# V831_CORE.net
KiCad netlist of a schematic drawn in Altium Designer
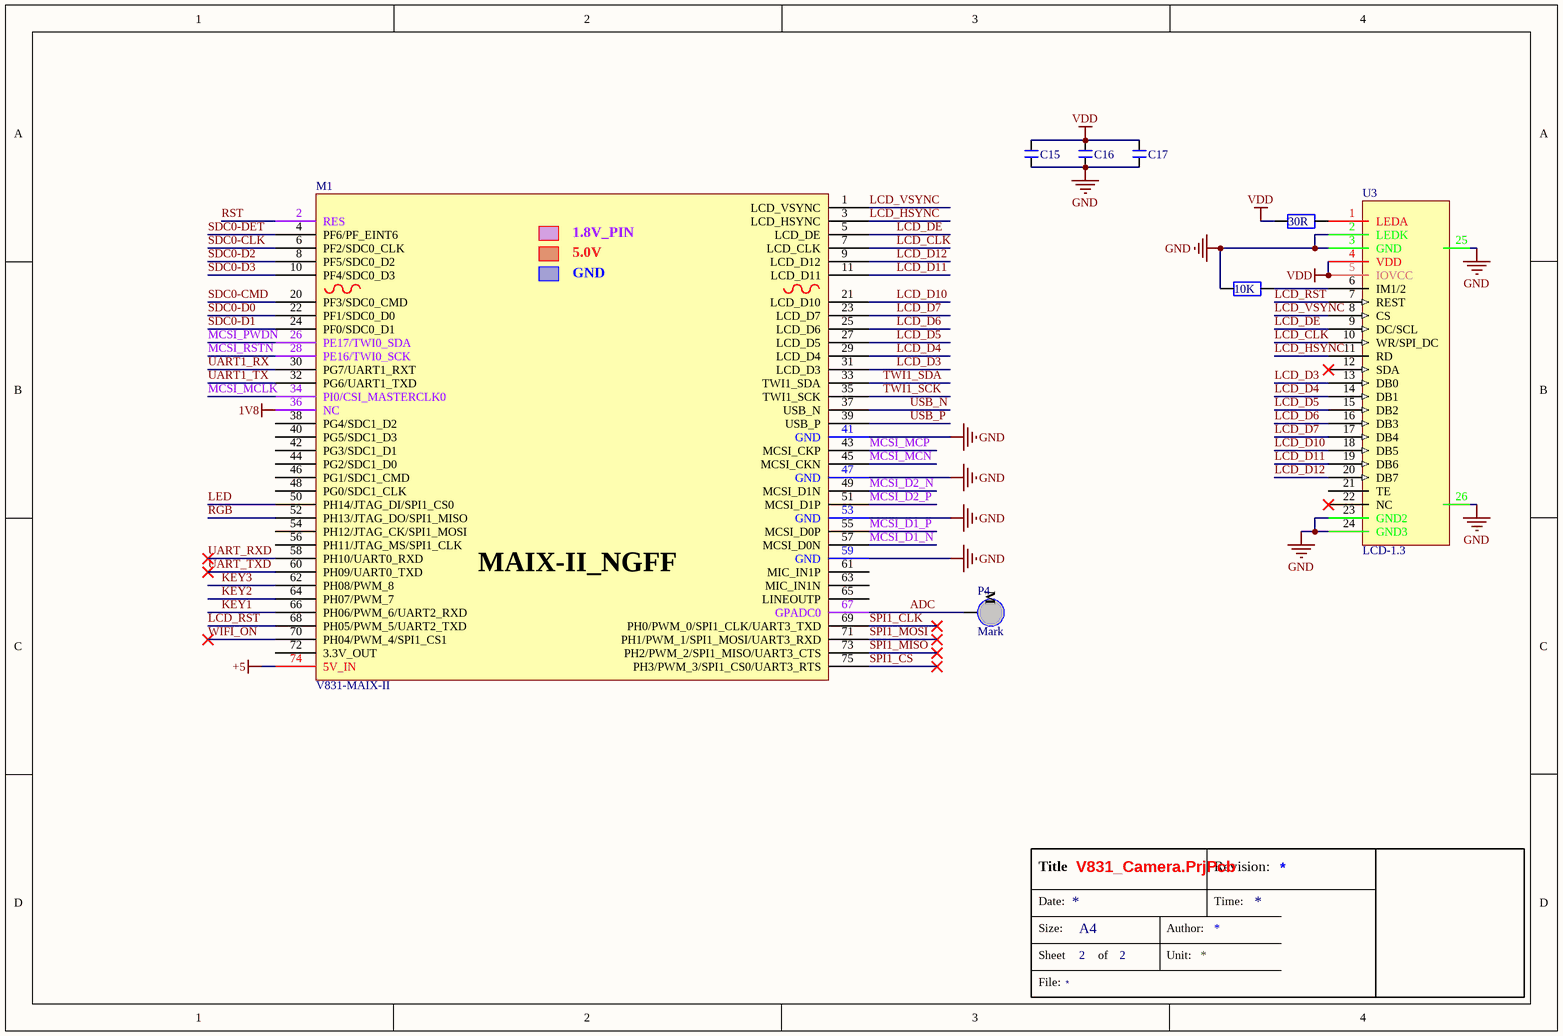
[diagram p0: V831_CORE.SchDoc]

(export (version "E")
  (design (tool "Eeschema 10.0.6"))
  (components
    (comp (ref "C15")
      (value "100NF")
      (footprint "CAP_0603")
      (description "CAP  12~50V")
      (libsource (lib "User") (part "CAP"))
    )
    (comp (ref "C16")
      (value "100NF")
      (footprint "CAP_0603")
      (description "CAP  12~50V")
      (libsource (lib "User") (part "CAP"))
    )
    (comp (ref "C17")
      (value "100NF")
      (footprint "CAP_0603")
      (description "CAP  12~50V")
      (libsource (lib "User") (part "CAP"))
    )
    (comp (ref "M1")
      (value "V831-MAIX-II")
      (footprint "V831_NAIX-II")
      (description "Sipeed-v831-M2dock")
      (libsource (lib "User") (part "V831_MAIX-II"))
    )
    (comp (ref "P4") (value "Mark") (footprint "Mark") (libsource (lib "User") (part "Mark")))
    (comp (ref "R15")
      (value "30R")
      (footprint "RESC_0603_2")
      (description "RES 贴片")
      (libsource (lib "User") (part "RES"))
    )
    (comp (ref "R16")
      (value "10K")
      (footprint "RESC_0603_2")
      (description "RES 贴片")
      (libsource (lib "User") (part "RES"))
    )
    (comp (ref "U3")
      (value "LCD-1.3")
      (footprint "FPC-24PIN-FB-Mirror")
      (description "SHOW  24Pin")
      (libsource (lib "User") (part "LCD_1.3"))
    )
  )
  (nets
    (net (code "1") (name "+5") (class "Default")
      (node (ref "M1") (pin "74") (pinfunction "5V_IN_74") (pintype "passive"))
    )
    (net (code "2") (name "/ADC") (class "Default")
      (node (ref "M1") (pin "67") (pinfunction "GPADC0_67") (pintype "passive"))
      (node (ref "P4") (pin "1") (pinfunction "1_1") (pintype "passive"))
    )
    (net (code "3") (name "/KEY1") (class "Default")
      (node (ref "M1") (pin "66") (pinfunction "PH06/PWM_6/UART2_RXD_66") (pintype "passive"))
    )
    (net (code "4") (name "/KEY2") (class "Default")
      (node (ref "M1") (pin "64") (pinfunction "PH07/PWM_7_64") (pintype "passive"))
    )
    (net (code "5") (name "/KEY3") (class "Default")
      (node (ref "M1") (pin "62") (pinfunction "PH08/PWM_8_62") (pintype "passive"))
    )
    (net (code "6") (name "/LCD_CLK") (class "Default")
      (node (ref "M1") (pin "7") (pinfunction "LCD_CLK_7") (pintype "passive"))
      (node (ref "U3") (pin "10") (pinfunction "WR/SPI_DC_10") (pintype "input"))
    )
    (net (code "7") (name "/LCD_D3") (class "Default")
      (node (ref "M1") (pin "31") (pinfunction "LCD_D3_31") (pintype "passive"))
      (node (ref "U3") (pin "13") (pinfunction "DB0_13") (pintype "input"))
    )
    (net (code "8") (name "/LCD_D4") (class "Default")
      (node (ref "M1") (pin "29") (pinfunction "LCD_D4_29") (pintype "passive"))
      (node (ref "U3") (pin "14") (pinfunction "DB1_14") (pintype "input"))
    )
    (net (code "9") (name "/LCD_D5") (class "Default")
      (node (ref "M1") (pin "27") (pinfunction "LCD_D5_27") (pintype "passive"))
      (node (ref "U3") (pin "15") (pinfunction "DB2_15") (pintype "input"))
    )
    (net (code "10") (name "/LCD_D6") (class "Default")
      (node (ref "M1") (pin "25") (pinfunction "LCD_D6_25") (pintype "passive"))
      (node (ref "U3") (pin "16") (pinfunction "DB3_16") (pintype "input"))
    )
    (net (code "11") (name "/LCD_D7") (class "Default")
      (node (ref "M1") (pin "23") (pinfunction "LCD_D7_23") (pintype "passive"))
      (node (ref "U3") (pin "17") (pinfunction "DB4_17") (pintype "input"))
    )
    (net (code "12") (name "/LCD_D10") (class "Default")
      (node (ref "M1") (pin "21") (pinfunction "LCD_D10_21") (pintype "passive"))
      (node (ref "U3") (pin "18") (pinfunction "DB5_18") (pintype "input"))
    )
    (net (code "13") (name "/LCD_D11") (class "Default")
      (node (ref "M1") (pin "11") (pinfunction "LCD_D11_11") (pintype "passive"))
      (node (ref "U3") (pin "19") (pinfunction "DB6_19") (pintype "input"))
    )
    (net (code "14") (name "/LCD_D12") (class "Default")
      (node (ref "M1") (pin "9") (pinfunction "LCD_D12_9") (pintype "passive"))
      (node (ref "U3") (pin "20") (pinfunction "DB7_20") (pintype "input"))
    )
    (net (code "15") (name "/LCD_DE") (class "Default")
      (node (ref "M1") (pin "5") (pinfunction "LCD_DE_5") (pintype "passive"))
      (node (ref "U3") (pin "9") (pinfunction "DC/SCL_9") (pintype "input"))
    )
    (net (code "16") (name "/LCD_HSYNC") (class "Default")
      (node (ref "M1") (pin "3") (pinfunction "LCD_HSYNC_3") (pintype "passive"))
      (node (ref "U3") (pin "11") (pinfunction "RD_11") (pintype "passive"))
    )
    (net (code "17") (name "/LCD_RST") (class "Default")
      (node (ref "M1") (pin "68") (pinfunction "PH05/PWM_5/UART2_TXD_68") (pintype "passive"))
      (node (ref "U3") (pin "7") (pinfunction "REST_7") (pintype "input"))
    )
    (net (code "18") (name "/LCD_VSYNC") (class "Default")
      (node (ref "M1") (pin "1") (pinfunction "LCD_VSYNC_1") (pintype "passive"))
      (node (ref "U3") (pin "8") (pinfunction "CS_8") (pintype "input"))
    )
    (net (code "19") (name "/LED") (class "Default")
      (node (ref "M1") (pin "50") (pinfunction "PH14/JTAG_DI/SPI1_CS0_50") (pintype "passive"))
    )
    (net (code "20") (name "/MCSI_D1_N") (class "Default")
      (node (ref "M1") (pin "57") (pinfunction "MCSI_D0N_57") (pintype "passive"))
    )
    (net (code "21") (name "/MCSI_D1_P") (class "Default")
      (node (ref "M1") (pin "55") (pinfunction "MCSI_D0P_55") (pintype "passive"))
    )
    (net (code "22") (name "/MCSI_D2_N") (class "Default")
      (node (ref "M1") (pin "49") (pinfunction "MCSI_D1N_49") (pintype "passive"))
    )
    (net (code "23") (name "/MCSI_D2_P") (class "Default")
      (node (ref "M1") (pin "51") (pinfunction "MCSI_D1P_51") (pintype "passive"))
    )
    (net (code "24") (name "/MCSI_MCLK") (class "Default")
      (node (ref "M1") (pin "34") (pinfunction "PI0/CSI_MASTERCLK0_34") (pintype "passive"))
    )
    (net (code "25") (name "/MCSI_MCN") (class "Default")
      (node (ref "M1") (pin "45") (pinfunction "MCSI_CKN_45") (pintype "passive"))
    )
    (net (code "26") (name "/MCSI_MCP") (class "Default")
      (node (ref "M1") (pin "43") (pinfunction "MCSI_CKP_43") (pintype "passive"))
    )
    (net (code "27") (name "/MCSI_PWDN") (class "Default")
      (node (ref "M1") (pin "26") (pinfunction "PE17/TWI0_SDA_26") (pintype "passive"))
    )
    (net (code "28") (name "/MCSI_RSTN") (class "Default")
      (node (ref "M1") (pin "28") (pinfunction "PE16/TWI0_SCK_28") (pintype "passive"))
    )
    (net (code "29") (name "/RGB") (class "Default")
      (node (ref "M1") (pin "52") (pinfunction "PH13/JTAG_DO/SPI1_MISO_52") (pintype "passive"))
    )
    (net (code "30") (name "/RST") (class "Default")
      (node (ref "M1") (pin "2") (pinfunction "RES_2") (pintype "passive"))
    )
    (net (code "31") (name "/SDC0-CLK") (class "Default")
      (node (ref "M1") (pin "6") (pinfunction "PF2/SDC0_CLK_6") (pintype "passive"))
    )
    (net (code "32") (name "/SDC0-CMD") (class "Default")
      (node (ref "M1") (pin "20") (pinfunction "PF3/SDC0_CMD_20") (pintype "passive"))
    )
    (net (code "33") (name "/SDC0-D0") (class "Default")
      (node (ref "M1") (pin "22") (pinfunction "PF1/SDC0_D0_22") (pintype "passive"))
    )
    (net (code "34") (name "/SDC0-D1") (class "Default")
      (node (ref "M1") (pin "24") (pinfunction "PF0/SDC0_D1_24") (pintype "passive"))
    )
    (net (code "35") (name "/SDC0-D2") (class "Default")
      (node (ref "M1") (pin "8") (pinfunction "PF5/SDC0_D2_8") (pintype "passive"))
    )
    (net (code "36") (name "/SDC0-D3") (class "Default")
      (node (ref "M1") (pin "10") (pinfunction "PF4/SDC0_D3_10") (pintype "passive"))
    )
    (net (code "37") (name "/SDC0-DET") (class "Default")
      (node (ref "M1") (pin "4") (pinfunction "PF6/PF_EINT6_4") (pintype "passive"))
    )
    (net (code "38") (name "/SPI1_CLK") (class "Default")
      (node (ref "M1") (pin "69") (pinfunction "PH0/PWM_0/SPI1_CLK/UART3_TXD_69") (pintype "passive+no_connect"))
    )
    (net (code "39") (name "/SPI1_CS") (class "Default")
      (node (ref "M1") (pin "75") (pinfunction "PH3/PWM_3/SPI1_CS0/UART3_RTS_75") (pintype "passive+no_connect"))
    )
    (net (code "40") (name "/SPI1_MISO") (class "Default")
      (node (ref "M1") (pin "73") (pinfunction "PH2/PWM_2/SPI1_MISO/UART3_CTS_73") (pintype "passive+no_connect"))
    )
    (net (code "41") (name "/SPI1_MOSI") (class "Default")
      (node (ref "M1") (pin "71") (pinfunction "PH1/PWM_1/SPI1_MOSI/UART3_RXD_71") (pintype "passive+no_connect"))
    )
    (net (code "42") (name "/TWI1_SCK") (class "Default")
      (node (ref "M1") (pin "35") (pinfunction "TWI1_SCK_35") (pintype "passive"))
    )
    (net (code "43") (name "/TWI1_SDA") (class "Default")
      (node (ref "M1") (pin "33") (pinfunction "TWI1_SDA_33") (pintype "passive"))
    )
    (net (code "44") (name "/UART1_RX") (class "Default")
      (node (ref "M1") (pin "30") (pinfunction "PG7/UART1_RXT_30") (pintype "passive"))
    )
    (net (code "45") (name "/UART1_TX") (class "Default")
      (node (ref "M1") (pin "32") (pinfunction "PG6/UART1_TXD_32") (pintype "passive"))
    )
    (net (code "46") (name "/UART_RXD") (class "Default")
      (node (ref "M1") (pin "58") (pinfunction "PH10/UART0_RXD_58") (pintype "passive+no_connect"))
    )
    (net (code "47") (name "/UART_TXD") (class "Default")
      (node (ref "M1") (pin "60") (pinfunction "PH09/UART0_TXD_60") (pintype "passive+no_connect"))
    )
    (net (code "48") (name "/USB_N") (class "Default")
      (node (ref "M1") (pin "37") (pinfunction "USB_N_37") (pintype "passive"))
    )
    (net (code "49") (name "/USB_P") (class "Default")
      (node (ref "M1") (pin "39") (pinfunction "USB_P_39") (pintype "passive"))
    )
    (net (code "50") (name "/WIFI_ON") (class "Default")
      (node (ref "M1") (pin "70") (pinfunction "PH04/PWM_4/SPI1_CS1_70") (pintype "passive+no_connect"))
    )
    (net (code "51") (name "1V8") (class "Default")
      (node (ref "M1") (pin "36") (pinfunction "NC_36") (pintype "passive"))
    )
    (net (code "52") (name "GND") (class "Default")
      (node (ref "C15") (pin "1") (pinfunction "0_1") (pintype "passive"))
      (node (ref "C16") (pin "1") (pinfunction "0_1") (pintype "passive"))
      (node (ref "C17") (pin "1") (pinfunction "0_1") (pintype "passive"))
      (node (ref "M1") (pin "41") (pinfunction "GND_41") (pintype "passive"))
      (node (ref "M1") (pin "47") (pinfunction "GND_47") (pintype "passive"))
      (node (ref "M1") (pin "53") (pinfunction "GND_53") (pintype "passive"))
      (node (ref "M1") (pin "59") (pinfunction "GND_59") (pintype "passive"))
      (node (ref "R16") (pin "2") (pinfunction "2_2") (pintype "passive"))
      (node (ref "U3") (pin "2") (pinfunction "LEDK_2") (pintype "passive"))
      (node (ref "U3") (pin "23") (pinfunction "GND2_23") (pintype "passive"))
      (node (ref "U3") (pin "24") (pinfunction "GND3_24") (pintype "passive"))
      (node (ref "U3") (pin "25") (pinfunction "GND_25") (pintype "passive"))
      (node (ref "U3") (pin "26") (pinfunction "GND_26") (pintype "passive"))
      (node (ref "U3") (pin "3") (pinfunction "GND_3") (pintype "passive"))
    )
    (net (code "53") (name "Net-(U3-IM1{slash}2)") (class "Default")
      (node (ref "R16") (pin "1") (pinfunction "1_1") (pintype "passive"))
      (node (ref "U3") (pin "6") (pinfunction "IM1/2_6") (pintype "passive"))
    )
    (net (code "54") (name "Net-(U3-LEDA)") (class "Default")
      (node (ref "R15") (pin "1") (pinfunction "1_1") (pintype "passive"))
      (node (ref "U3") (pin "1") (pinfunction "LEDA_1") (pintype "power_in"))
    )
    (net (code "55") (name "VDD") (class "Default")
      (node (ref "C15") (pin "2") (pinfunction "0_2") (pintype "passive"))
      (node (ref "C16") (pin "2") (pinfunction "0_2") (pintype "passive"))
      (node (ref "C17") (pin "2") (pinfunction "0_2") (pintype "passive"))
      (node (ref "R15") (pin "2") (pinfunction "2_2") (pintype "passive"))
      (node (ref "U3") (pin "4") (pinfunction "VDD_4") (pintype "passive"))
      (node (ref "U3") (pin "5") (pinfunction "IOVCC_5") (pintype "passive"))
    )
    (net (code "56") (name "unconnected-(M1-3.3V_OUT-Pad72)") (class "Default")
      (node (ref "M1") (pin "72") (pinfunction "3.3V_OUT_72") (pintype "passive"))
    )
    (net (code "57") (name "unconnected-(M1-LINEOUTP-Pad65)") (class "Default")
      (node (ref "M1") (pin "65") (pinfunction "LINEOUTP_65") (pintype "passive"))
    )
    (net (code "58") (name "unconnected-(M1-MIC_IN1N-Pad63)") (class "Default")
      (node (ref "M1") (pin "63") (pinfunction "MIC_IN1N_63") (pintype "passive"))
    )
    (net (code "59") (name "unconnected-(M1-MIC_IN1P-Pad61)") (class "Default")
      (node (ref "M1") (pin "61") (pinfunction "MIC_IN1P_61") (pintype "passive"))
    )
    (net (code "60") (name "unconnected-(M1-PG0{slash}SDC1_CLK-Pad48)") (class "Default")
      (node (ref "M1") (pin "48") (pinfunction "PG0/SDC1_CLK_48") (pintype "passive"))
    )
    (net (code "61") (name "unconnected-(M1-PG1{slash}SDC1_CMD-Pad46)") (class "Default")
      (node (ref "M1") (pin "46") (pinfunction "PG1/SDC1_CMD_46") (pintype "passive"))
    )
    (net (code "62") (name "unconnected-(M1-PG2{slash}SDC1_D0-Pad44)") (class "Default")
      (node (ref "M1") (pin "44") (pinfunction "PG2/SDC1_D0_44") (pintype "passive"))
    )
    (net (code "63") (name "unconnected-(M1-PG3{slash}SDC1_D1-Pad42)") (class "Default")
      (node (ref "M1") (pin "42") (pinfunction "PG3/SDC1_D1_42") (pintype "passive"))
    )
    (net (code "64") (name "unconnected-(M1-PG4{slash}SDC1_D2-Pad38)") (class "Default")
      (node (ref "M1") (pin "38") (pinfunction "PG4/SDC1_D2_38") (pintype "passive"))
    )
    (net (code "65") (name "unconnected-(M1-PG5{slash}SDC1_D3-Pad40)") (class "Default")
      (node (ref "M1") (pin "40") (pinfunction "PG5/SDC1_D3_40") (pintype "passive"))
    )
    (net (code "66") (name "unconnected-(M1-PH11{slash}JTAG_MS{slash}SPI1_CLK-Pad56)") (class "Default")
      (node (ref "M1") (pin "56") (pinfunction "PH11/JTAG_MS/SPI1_CLK_56") (pintype "passive"))
    )
    (net (code "67") (name "unconnected-(M1-PH12{slash}JTAG_CK{slash}SPI1_MOSI-Pad54)") (class "Default")
      (node (ref "M1") (pin "54") (pinfunction "PH12/JTAG_CK/SPI1_MOSI_54") (pintype "passive"))
    )
    (net (code "68") (name "unconnected-(U3-NC-Pad22)") (class "Default")
      (node (ref "U3") (pin "22") (pinfunction "NC_22") (pintype "passive+no_connect"))
    )
    (net (code "69") (name "unconnected-(U3-SDA-Pad12)") (class "Default")
      (node (ref "U3") (pin "12") (pinfunction "SDA_12") (pintype "input+no_connect"))
    )
    (net (code "70") (name "unconnected-(U3-TE-Pad21)") (class "Default")
      (node (ref "U3") (pin "21") (pinfunction "TE_21") (pintype "passive"))
    )
  )
)
